# uSD_socket_breakout_rev_2.net
KiCad netlist of a schematic drawn in EAGLE
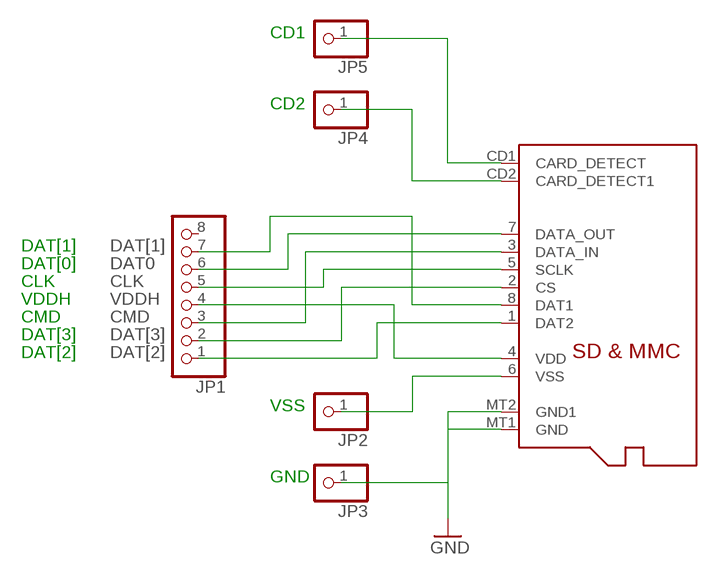
[diagram p0: schematic, sheet 1]

(export (version "E")
  (design (tool "Eeschema 10.0.6"))
  (components
    (comp (ref "JP1")
      (value "PINHD-1X8CLEANBIG")
      (footprint "eagle-import:1X08-CLEANBIG")
      (libsource (lib "eagle-import") (part "PINHD-1X8CLEANBIG"))
    )
    (comp (ref "JP2")
      (value "PINHD-1X1CB")
      (footprint "eagle-import:1X01-CLEANBIG")
      (libsource (lib "eagle-import") (part "PINHD-1X1CB"))
    )
    (comp (ref "JP3")
      (value "PINHD-1X1CB")
      (footprint "eagle-import:1X01-CLEANBIG")
      (libsource (lib "eagle-import") (part "PINHD-1X1CB"))
    )
    (comp (ref "JP4")
      (value "PINHD-1X1CB")
      (footprint "eagle-import:1X01-CLEANBIG")
      (libsource (lib "eagle-import") (part "PINHD-1X1CB"))
    )
    (comp (ref "JP5")
      (value "PINHD-1X1CB")
      (footprint "eagle-import:1X01-CLEANBIG")
      (libsource (lib "eagle-import") (part "PINHD-1X1CB"))
    )
    (comp (ref "U$1")
      (value "MICROSD")
      (footprint "eagle-import:MICROSD")
      (libsource (lib "eagle-import") (part "MICROSD"))
    )
  )
  (nets
    (net (code "1") (name "/CLK") (class "Default")
      (node (ref "JP1") (pin "5") (pinfunction "5_5") (pintype "passive"))
      (node (ref "U$1") (pin "5") (pinfunction "SCLK_5") (pintype "input"))
    )
    (net (code "2") (name "/CMD") (class "Default")
      (node (ref "JP1") (pin "3") (pinfunction "3_3") (pintype "passive"))
      (node (ref "U$1") (pin "3") (pinfunction "DATA_IN_3") (pintype "input"))
    )
    (net (code "3") (name "/DAT0") (class "Default")
      (node (ref "JP1") (pin "6") (pinfunction "6_6") (pintype "passive"))
      (node (ref "U$1") (pin "7") (pinfunction "DATA_OUT_7") (pintype "output"))
    )
    (net (code "4") (name "/DAT[1]") (class "Default")
      (node (ref "JP1") (pin "7") (pinfunction "7_7") (pintype "passive"))
      (node (ref "U$1") (pin "8") (pinfunction "DAT1_8") (pintype "bidirectional"))
    )
    (net (code "5") (name "/DAT[2]") (class "Default")
      (node (ref "JP1") (pin "1") (pinfunction "1_1") (pintype "passive"))
      (node (ref "U$1") (pin "1") (pinfunction "DAT2_1") (pintype "bidirectional"))
    )
    (net (code "6") (name "/DAT[3]") (class "Default")
      (node (ref "JP1") (pin "2") (pinfunction "2_2") (pintype "passive"))
      (node (ref "U$1") (pin "2") (pinfunction "CS_2") (pintype "input"))
    )
    (net (code "7") (name "/VDDH") (class "Default")
      (node (ref "JP1") (pin "4") (pinfunction "4_4") (pintype "passive"))
      (node (ref "U$1") (pin "4") (pinfunction "VDD_4") (pintype "power_in"))
    )
    (net (code "8") (name "GND") (class "Default")
      (node (ref "JP3") (pin "1") (pinfunction "1_1") (pintype "passive"))
      (node (ref "U$1") (pin "MT1") (pinfunction "GND_MT1") (pintype "power_in"))
      (node (ref "U$1") (pin "MT2") (pinfunction "GND1_MT2") (pintype "power_in"))
    )
    (net (code "9") (name "Net-(U$1-CARD_DETECT)") (class "Default")
      (node (ref "JP5") (pin "1") (pinfunction "1_1") (pintype "passive"))
      (node (ref "U$1") (pin "CD1") (pinfunction "CARD_DETECT_CD1") (pintype "passive"))
    )
    (net (code "10") (name "Net-(U$1-CARD_DETECT1)") (class "Default")
      (node (ref "JP4") (pin "1") (pinfunction "1_1") (pintype "passive"))
      (node (ref "U$1") (pin "CD2") (pinfunction "CARD_DETECT1_CD2") (pintype "passive"))
    )
    (net (code "11") (name "Net-(U$1-VSS)") (class "Default")
      (node (ref "JP2") (pin "1") (pinfunction "1_1") (pintype "passive"))
      (node (ref "U$1") (pin "6") (pinfunction "VSS_6") (pintype "power_in"))
    )
    (net (code "12") (name "unconnected-(JP1-Pad8)") (class "Default")
      (node (ref "JP1") (pin "8") (pinfunction "8_8") (pintype "passive"))
    )
  )
)
